# emmcdisable.net
KiCad netlist of a schematic drawn in EAGLE
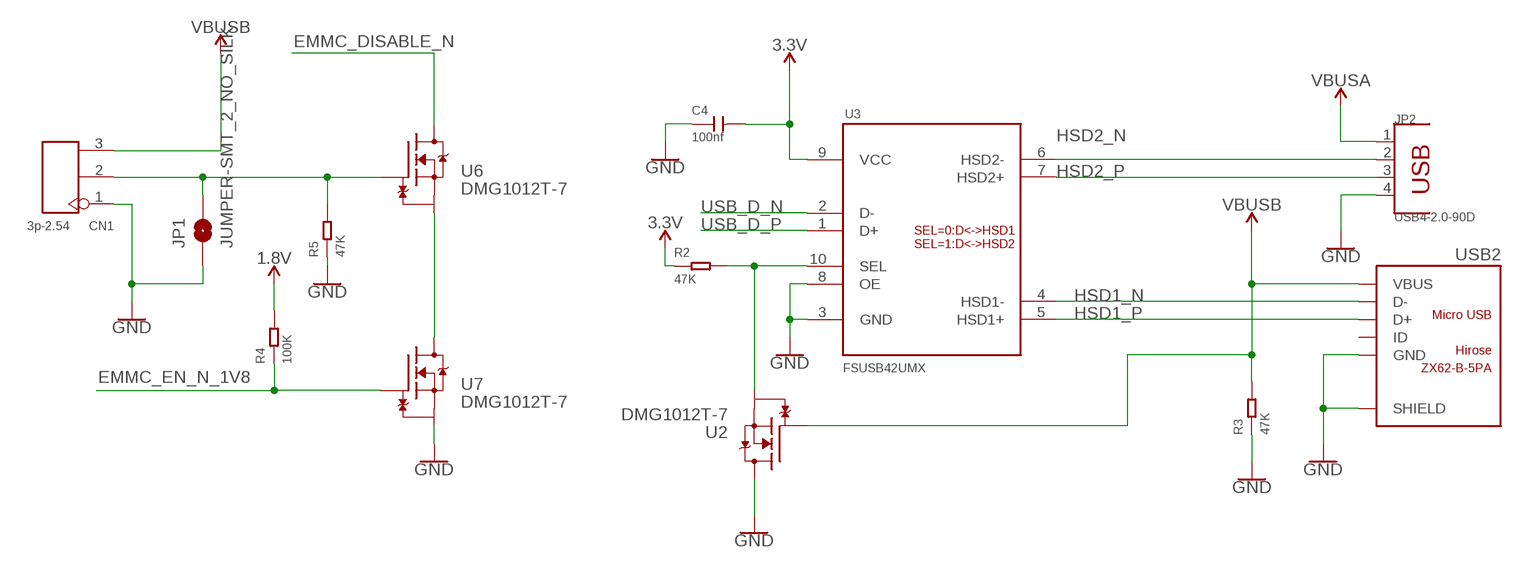
[diagram p0: schematic, sheet 1]

(export (version "E")
  (design (tool "Eeschema 10.0.6"))
  (components
    (comp (ref "C4")
      (value "100nf")
      (footprint "eagle-import:C0402K")
      (fields (field (name "MPN") "CC0402KRX7R8BB104"))
      (libsource (lib "eagle-import") (part "CERAMIC-100NF-25V-10%-X7R(0402)"))
    )
    (comp (ref "CN1")
      (value "3p-2.54")
      (footprint "eagle-import:H3-2.54")
      (libsource (lib "eagle-import") (part "DIP-BLACK-MALE-HEADER-VERT(3P-2.54)"))
    )
    (comp (ref "JP1")
      (value "JUMPER-SMT_2_NO_SILK")
      (footprint "eagle-import:SMT-JUMPER_2_NO_SILK")
      (libsource (lib "eagle-import") (part "JUMPER-SMT_2_NO_SILK"))
    )
    (comp (ref "JP2")
      (value "USB4-2.0-90D")
      (footprint "eagle-import:USB4+2P-2.0-90D")
      (libsource (lib "eagle-import") (part "DIP-USB-A-TYPE-FMAL(4+2P-2.0-90D)"))
    )
    (comp (ref "R2")
      (value "47K")
      (footprint "eagle-import:R0402")
      (fields (field (name "MPN") "RC0402JR-0747KL"))
      (libsource (lib "eagle-import") (part "SMD-RES-47K-5%-1/16W(0402)"))
    )
    (comp (ref "R3")
      (value "47K")
      (footprint "eagle-import:R0402")
      (fields (field (name "MPN") "RC0402JR-0747KL"))
      (libsource (lib "eagle-import") (part "SMD-RES-47K-5%-1/16W(0402)"))
    )
    (comp (ref "R4")
      (value "100K")
      (footprint "eagle-import:R0402")
      (fields (field (name "MPN") "RC0402FR-07100KL"))
      (libsource (lib "eagle-import") (part "SMD-RES-100K-1%-1/16W(0402)"))
    )
    (comp (ref "R5")
      (value "47K")
      (footprint "eagle-import:R0402")
      (fields (field (name "MPN") "RC0402JR-0747KL"))
      (libsource (lib "eagle-import") (part "SMD-RES-47K-5%-1/16W(0402)"))
    )
    (comp (ref "U2")
      (value "DMG1012T-7")
      (footprint "eagle-import:SOT50P175X90-3N")
      (libsource (lib "eagle-import") (part "DMG1012T-7"))
    )
    (comp (ref "U3")
      (value "FSUSB42UMX")
      (footprint "eagle-import:QFN40P140X180X55-10")
      (libsource (lib "eagle-import") (part "FSUSB42UMX"))
    )
    (comp (ref "U6")
      (value "DMG1012T-7")
      (footprint "eagle-import:SOT50P175X90-3N")
      (libsource (lib "eagle-import") (part "DMG1012T-7"))
    )
    (comp (ref "U7")
      (value "DMG1012T-7")
      (footprint "eagle-import:SOT50P175X90-3N")
      (libsource (lib "eagle-import") (part "DMG1012T-7"))
    )
    (comp (ref "USB2")
      (value "ZX62-B-5PA")
      (footprint "eagle-import:MICRO-USB5+6P-SMD-0.65-AB")
      (libsource (lib "eagle-import") (part "MICRO-USB-SMD(ZX62-B-5PA)"))
    )
  )
  (nets
    (net (code "1") (name "/EMMC_DISABLE_N") (class "Default")
      (node (ref "U6") (pin "D") (pinfunction "D_D") (pintype "passive"))
    )
    (net (code "2") (name "/EMMC_EN_N_1V8") (class "Default")
      (node (ref "R4") (pin "1") (pinfunction "1_1") (pintype "passive"))
      (node (ref "U7") (pin "G") (pinfunction "G_G") (pintype "passive"))
    )
    (net (code "3") (name "/HSD1_N") (class "Default")
      (node (ref "U3") (pin "4") (pinfunction "HSD1-_4") (pintype "bidirectional"))
      (node (ref "USB2") (pin "2") (pinfunction "D-_2") (pintype "bidirectional"))
    )
    (net (code "4") (name "/HSD1_P") (class "Default")
      (node (ref "U3") (pin "5") (pinfunction "HSD1+_5") (pintype "bidirectional"))
      (node (ref "USB2") (pin "3") (pinfunction "D+_3") (pintype "bidirectional"))
    )
    (net (code "5") (name "/HSD2_N") (class "Default")
      (node (ref "JP2") (pin "2") (pinfunction "2_2") (pintype "bidirectional"))
      (node (ref "U3") (pin "6") (pinfunction "HSD2-_6") (pintype "bidirectional"))
    )
    (net (code "6") (name "/HSD2_P") (class "Default")
      (node (ref "JP2") (pin "3") (pinfunction "3_3") (pintype "bidirectional"))
      (node (ref "U3") (pin "7") (pinfunction "HSD2+_7") (pintype "bidirectional"))
    )
    (net (code "7") (name "/USB_D_N") (class "Default")
      (node (ref "U3") (pin "2") (pinfunction "D-_2") (pintype "bidirectional"))
    )
    (net (code "8") (name "/USB_D_P") (class "Default")
      (node (ref "U3") (pin "1") (pinfunction "D+_1") (pintype "bidirectional"))
    )
    (net (code "9") (name "1.8V") (class "Default")
      (node (ref "R4") (pin "2") (pinfunction "2_2") (pintype "passive"))
    )
    (net (code "10") (name "3.3V") (class "Default")
      (node (ref "C4") (pin "2") (pinfunction "2_2") (pintype "passive"))
      (node (ref "R2") (pin "1") (pinfunction "1_1") (pintype "passive"))
      (node (ref "U3") (pin "9") (pinfunction "VCC_9") (pintype "power_in"))
    )
    (net (code "11") (name "GND") (class "Default")
      (node (ref "C4") (pin "1") (pinfunction "1_1") (pintype "passive"))
      (node (ref "CN1") (pin "1") (pinfunction "P$1_1") (pintype "bidirectional"))
      (node (ref "JP1") (pin "1") (pinfunction "1_1") (pintype "passive"))
      (node (ref "JP2") (pin "4") (pinfunction "4_4") (pintype "bidirectional"))
      (node (ref "R3") (pin "1") (pinfunction "1_1") (pintype "passive"))
      (node (ref "R5") (pin "1") (pinfunction "1_1") (pintype "passive"))
      (node (ref "U2") (pin "D") (pinfunction "D_D") (pintype "passive"))
      (node (ref "U3") (pin "3") (pinfunction "GND_3") (pintype "power_in"))
      (node (ref "U3") (pin "8") (pinfunction "OE_8") (pintype "input"))
      (node (ref "U7") (pin "S") (pinfunction "S_S") (pintype "passive"))
      (node (ref "USB2") (pin "5") (pinfunction "GND_5") (pintype "power_in"))
      (node (ref "USB2") (pin "P1") (pinfunction "SHIELD_P1") (pintype "power_in"))
      (node (ref "USB2") (pin "P2") (pinfunction "SHIELD_P2") (pintype "power_in"))
      (node (ref "USB2") (pin "P3") (pinfunction "SHIELD_P3") (pintype "power_in"))
      (node (ref "USB2") (pin "P4") (pinfunction "SHIELD_P4") (pintype "power_in"))
      (node (ref "USB2") (pin "P5") (pinfunction "SHIELD_P5") (pintype "power_in"))
      (node (ref "USB2") (pin "P6") (pinfunction "SHIELD_P6") (pintype "power_in"))
    )
    (net (code "12") (name "Net-(CN1-P$2)") (class "Default")
      (node (ref "CN1") (pin "2") (pinfunction "P$2_2") (pintype "bidirectional"))
      (node (ref "JP1") (pin "2") (pinfunction "2_2") (pintype "passive"))
      (node (ref "R5") (pin "2") (pinfunction "2_2") (pintype "passive"))
      (node (ref "U6") (pin "G") (pinfunction "G_G") (pintype "passive"))
    )
    (net (code "13") (name "Net-(U3-SEL)") (class "Default")
      (node (ref "R2") (pin "2") (pinfunction "2_2") (pintype "passive"))
      (node (ref "U2") (pin "S") (pinfunction "S_S") (pintype "passive"))
      (node (ref "U3") (pin "10") (pinfunction "SEL_10") (pintype "input"))
    )
    (net (code "14") (name "Net-(U6-PadS)") (class "Default")
      (node (ref "U6") (pin "S") (pinfunction "S_S") (pintype "passive"))
      (node (ref "U7") (pin "D") (pinfunction "D_D") (pintype "passive"))
    )
    (net (code "15") (name "VBUSA") (class "Default")
      (node (ref "JP2") (pin "1") (pinfunction "1_1") (pintype "bidirectional"))
    )
    (net (code "16") (name "VBUSB") (class "Default")
      (node (ref "CN1") (pin "3") (pinfunction "P$3_3") (pintype "bidirectional"))
      (node (ref "R3") (pin "2") (pinfunction "2_2") (pintype "passive"))
      (node (ref "U2") (pin "G") (pinfunction "G_G") (pintype "passive"))
      (node (ref "USB2") (pin "1") (pinfunction "VBUS_1") (pintype "power_in"))
    )
    (net (code "17") (name "unconnected-(USB2-ID-Pad4)") (class "Default")
      (node (ref "USB2") (pin "4") (pinfunction "ID_4") (pintype "bidirectional"))
    )
  )
)
